# Energy_SensorRevB.net
KiCad netlist of a schematic drawn in EAGLE
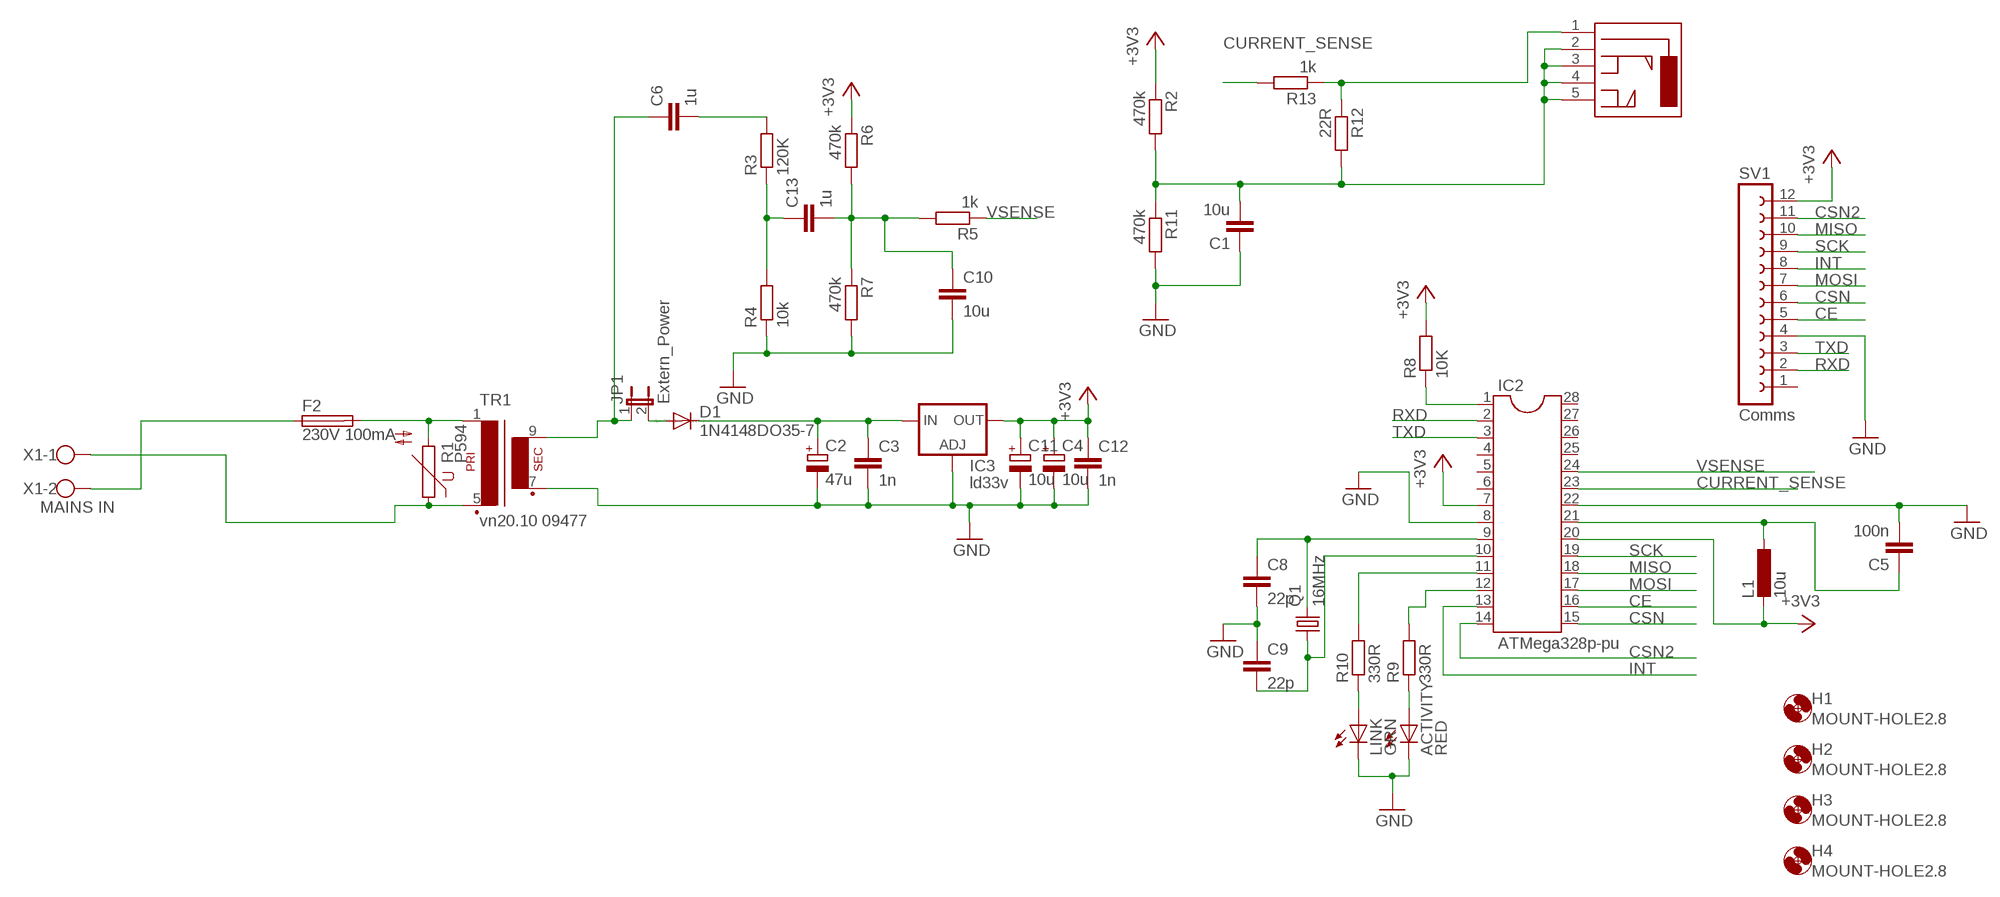
[diagram p0: schematic, sheet 1]

(export (version "E")
  (design (tool "Eeschema 10.0.6"))
  (components
    (comp (ref "ACTIVITY")
      (value "RED")
      (footprint "eagle-import:LED5MM")
      (libsource (lib "eagle-import") (part "LED5MM"))
    )
    (comp (ref "C1")
      (value "10u")
      (footprint "eagle-import:C1206K")
      (libsource (lib "eagle-import") (part "C-EUC1206K"))
    )
    (comp (ref "C2")
      (value "47u")
      (footprint "eagle-import:E3,5-10")
      (libsource (lib "eagle-import") (part "CPOL-EUE3.5-10"))
    )
    (comp (ref "C3")
      (value "1n")
      (footprint "eagle-import:C025-025X050")
      (libsource (lib "eagle-import") (part "C-EU025-025X050"))
    )
    (comp (ref "C4")
      (value "10u")
      (footprint "eagle-import:E3,5-8")
      (libsource (lib "eagle-import") (part "CPOL-EUE3.5-8"))
    )
    (comp (ref "C5")
      (value "100n")
      (footprint "eagle-import:C1206K")
      (libsource (lib "eagle-import") (part "C-EUC1206K"))
    )
    (comp (ref "C6")
      (value "1u")
      (footprint "eagle-import:C1206K")
      (libsource (lib "eagle-import") (part "C-EUC1206K"))
    )
    (comp (ref "C8")
      (value "22p")
      (footprint "eagle-import:C025-025X050")
      (libsource (lib "eagle-import") (part "C-EU025-025X050"))
    )
    (comp (ref "C9")
      (value "22p")
      (footprint "eagle-import:C025-025X050")
      (libsource (lib "eagle-import") (part "C-EU025-025X050"))
    )
    (comp (ref "C10")
      (value "10u")
      (footprint "eagle-import:C1206K")
      (libsource (lib "eagle-import") (part "C-EUC1206K"))
    )
    (comp (ref "C11")
      (value "10u")
      (footprint "eagle-import:E3,5-8")
      (libsource (lib "eagle-import") (part "CPOL-EUE3.5-8"))
    )
    (comp (ref "C12")
      (value "1n")
      (footprint "eagle-import:C025-025X050")
      (libsource (lib "eagle-import") (part "C-EU025-025X050"))
    )
    (comp (ref "C13")
      (value "1u")
      (footprint "eagle-import:C1206K")
      (libsource (lib "eagle-import") (part "C-EUC1206K"))
    )
    (comp (ref "D1")
      (value "1N4148DO35-7")
      (footprint "eagle-import:DO35-7")
      (libsource (lib "eagle-import") (part "1N4148DO35-7"))
    )
    (comp (ref "F2")
      (value "230V 100mA")
      (footprint "eagle-import:SH22,5A")
      (fields (field (name "MPN") "0031.7701.11"))
      (libsource (lib "eagle-import") (part "SH22,5A"))
    )
    (comp (ref "H1")
      (value "MOUNT-HOLE2.8")
      (footprint "eagle-import:2,8")
      (libsource (lib "eagle-import") (part "MOUNT-HOLE2.8"))
    )
    (comp (ref "H2")
      (value "MOUNT-HOLE2.8")
      (footprint "eagle-import:2,8")
      (libsource (lib "eagle-import") (part "MOUNT-HOLE2.8"))
    )
    (comp (ref "H3")
      (value "MOUNT-HOLE2.8")
      (footprint "eagle-import:2,8")
      (libsource (lib "eagle-import") (part "MOUNT-HOLE2.8"))
    )
    (comp (ref "H4")
      (value "MOUNT-HOLE2.8")
      (footprint "eagle-import:2,8")
      (libsource (lib "eagle-import") (part "MOUNT-HOLE2.8"))
    )
    (comp (ref "IC2")
      (value "ATMega328p-pu")
      (footprint "eagle-import:DIL28-3")
      (libsource (lib "eagle-import") (part "DIL28-3"))
    )
    (comp (ref "IC3")
      (value "ld33v")
      (footprint "eagle-import:317TL")
      (libsource (lib "eagle-import") (part "LM317TL"))
    )
    (comp (ref "JP1")
      (value "Extern_Power")
      (footprint "eagle-import:JP1")
      (libsource (lib "eagle-import") (part "JP1E"))
    )
    (comp (ref "L1")
      (value "10u")
      (footprint "eagle-import:L3230M")
      (libsource (lib "eagle-import") (part "L-EUL3230M"))
    )
    (comp (ref "LINK")
      (value "GRN")
      (footprint "eagle-import:LED5MM")
      (libsource (lib "eagle-import") (part "LED5MM"))
    )
    (comp (ref "Q1")
      (value "16MHz")
      (footprint "eagle-import:HC49_S")
      (libsource (lib "eagle-import") (part "CRYSTALHC49S"))
    )
    (comp (ref "R1")
      (value "P594")
      (footprint "eagle-import:P594")
      (libsource (lib "eagle-import") (part "P594"))
    )
    (comp (ref "R2")
      (value "470k")
      (footprint "eagle-import:0207_7")
      (libsource (lib "eagle-import") (part "R-EU_0207/7"))
    )
    (comp (ref "R3")
      (value "120K")
      (footprint "eagle-import:0207_7")
      (libsource (lib "eagle-import") (part "R-EU_0207/7"))
    )
    (comp (ref "R4")
      (value "10k")
      (footprint "eagle-import:0207_7")
      (libsource (lib "eagle-import") (part "R-EU_0207/7"))
    )
    (comp (ref "R5")
      (value "1k")
      (footprint "eagle-import:0207_7")
      (libsource (lib "eagle-import") (part "R-EU_0207/7"))
    )
    (comp (ref "R6")
      (value "470k")
      (footprint "eagle-import:0207_7")
      (libsource (lib "eagle-import") (part "R-EU_0207/7"))
    )
    (comp (ref "R7")
      (value "470k")
      (footprint "eagle-import:0207_7")
      (libsource (lib "eagle-import") (part "R-EU_0207/7"))
    )
    (comp (ref "R8")
      (value "10K")
      (footprint "eagle-import:0207_7")
      (libsource (lib "eagle-import") (part "R-EU_0207/7"))
    )
    (comp (ref "R9")
      (value "330R")
      (footprint "eagle-import:0207_7")
      (libsource (lib "eagle-import") (part "R-EU_0207/7"))
    )
    (comp (ref "R10")
      (value "330R")
      (footprint "eagle-import:0207_7")
      (libsource (lib "eagle-import") (part "R-EU_0207/7"))
    )
    (comp (ref "R11")
      (value "470k")
      (footprint "eagle-import:0207_7")
      (libsource (lib "eagle-import") (part "R-EU_0207/7"))
    )
    (comp (ref "R12")
      (value "22R")
      (footprint "eagle-import:R1206")
      (libsource (lib "eagle-import") (part "R-EU_R1206"))
    )
    (comp (ref "R13")
      (value "1k")
      (footprint "eagle-import:0207_7")
      (libsource (lib "eagle-import") (part "R-EU_0207/7"))
    )
    (comp (ref "SV1")
      (value "Comms")
      (footprint "eagle-import:FE12W")
      (libsource (lib "eagle-import") (part "FE12W"))
    )
    (comp (ref "TR1")
      (value "vn20.10 09477")
      (footprint "eagle-import:VV11")
      (libsource (lib "eagle-import") (part "VV11"))
    )
    (comp (ref "U$1")
      (value "3.5MMJACK")
      (footprint "eagle-import:3.5MMJACK")
      (libsource (lib "eagle-import") (part "3.5MMJACK"))
    )
    (comp (ref "X1")
      (value "MAINS IN")
      (footprint "eagle-import:W237-102")
      (fields (field (name "MPN") "237-102"))
      (libsource (lib "eagle-import") (part "W237-102"))
    )
  )
  (nets
    (net (code "1") (name "+3V3") (class "Default")
      (node (ref "C11") (pin "+") (pinfunction "+_+") (pintype "passive"))
      (node (ref "C12") (pin "1") (pinfunction "1_1") (pintype "passive"))
      (node (ref "C4") (pin "+") (pinfunction "+_+") (pintype "passive"))
      (node (ref "IC2") (pin "20") (pinfunction "20_20") (pintype "passive"))
      (node (ref "IC2") (pin "7") (pinfunction "7_7") (pintype "passive"))
      (node (ref "IC3") (pin "2") (pinfunction "OUT_2") (pintype "passive"))
      (node (ref "L1") (pin "2") (pinfunction "2_2") (pintype "passive"))
      (node (ref "R2") (pin "1") (pinfunction "1_1") (pintype "passive"))
      (node (ref "R6") (pin "1") (pinfunction "1_1") (pintype "passive"))
      (node (ref "R8") (pin "2") (pinfunction "2_2") (pintype "passive"))
      (node (ref "SV1") (pin "12") (pinfunction "12_12") (pintype "passive"))
    )
    (net (code "2") (name "/CE") (class "Default")
      (node (ref "IC2") (pin "16") (pinfunction "16_16") (pintype "passive"))
      (node (ref "SV1") (pin "5") (pinfunction "5_5") (pintype "passive"))
    )
    (net (code "3") (name "/CSN") (class "Default")
      (node (ref "IC2") (pin "15") (pinfunction "15_15") (pintype "passive"))
      (node (ref "SV1") (pin "6") (pinfunction "6_6") (pintype "passive"))
    )
    (net (code "4") (name "/CSN2") (class "Default")
      (node (ref "IC2") (pin "14") (pinfunction "14_14") (pintype "passive"))
      (node (ref "SV1") (pin "11") (pinfunction "11_11") (pintype "passive"))
    )
    (net (code "5") (name "/CURRENT_SENSE") (class "Default")
      (node (ref "IC2") (pin "23") (pinfunction "23_23") (pintype "passive"))
      (node (ref "R13") (pin "2") (pinfunction "2_2") (pintype "passive"))
    )
    (net (code "6") (name "/INT") (class "Default")
      (node (ref "IC2") (pin "13") (pinfunction "13_13") (pintype "passive"))
      (node (ref "SV1") (pin "8") (pinfunction "8_8") (pintype "passive"))
    )
    (net (code "7") (name "/MISO") (class "Default")
      (node (ref "IC2") (pin "18") (pinfunction "18_18") (pintype "passive"))
      (node (ref "SV1") (pin "10") (pinfunction "10_10") (pintype "passive"))
    )
    (net (code "8") (name "/MOSI") (class "Default")
      (node (ref "IC2") (pin "17") (pinfunction "17_17") (pintype "passive"))
      (node (ref "SV1") (pin "7") (pinfunction "7_7") (pintype "passive"))
    )
    (net (code "9") (name "/RXD") (class "Default")
      (node (ref "IC2") (pin "2") (pinfunction "2_2") (pintype "passive"))
      (node (ref "SV1") (pin "2") (pinfunction "2_2") (pintype "passive"))
    )
    (net (code "10") (name "/SCK") (class "Default")
      (node (ref "IC2") (pin "19") (pinfunction "19_19") (pintype "passive"))
      (node (ref "SV1") (pin "9") (pinfunction "9_9") (pintype "passive"))
    )
    (net (code "11") (name "/TXD") (class "Default")
      (node (ref "IC2") (pin "3") (pinfunction "3_3") (pintype "passive"))
      (node (ref "SV1") (pin "3") (pinfunction "3_3") (pintype "passive"))
    )
    (net (code "12") (name "/VSENSE") (class "Default")
      (node (ref "IC2") (pin "24") (pinfunction "24_24") (pintype "passive"))
      (node (ref "R5") (pin "1") (pinfunction "1_1") (pintype "passive"))
    )
    (net (code "13") (name "GND") (class "Default")
      (node (ref "ACTIVITY") (pin "K") (pinfunction "C_K") (pintype "passive"))
      (node (ref "C1") (pin "1") (pinfunction "1_1") (pintype "passive"))
      (node (ref "C10") (pin "2") (pinfunction "2_2") (pintype "passive"))
      (node (ref "C11") (pin "-") (pinfunction "-_-") (pintype "passive"))
      (node (ref "C12") (pin "2") (pinfunction "2_2") (pintype "passive"))
      (node (ref "C2") (pin "-") (pinfunction "-_-") (pintype "passive"))
      (node (ref "C3") (pin "2") (pinfunction "2_2") (pintype "passive"))
      (node (ref "C4") (pin "-") (pinfunction "-_-") (pintype "passive"))
      (node (ref "C5") (pin "2") (pinfunction "2_2") (pintype "passive"))
      (node (ref "C8") (pin "2") (pinfunction "2_2") (pintype "passive"))
      (node (ref "C9") (pin "1") (pinfunction "1_1") (pintype "passive"))
      (node (ref "IC2") (pin "22") (pinfunction "22_22") (pintype "passive"))
      (node (ref "IC2") (pin "8") (pinfunction "8_8") (pintype "passive"))
      (node (ref "IC3") (pin "1") (pinfunction "ADJ_1") (pintype "input"))
      (node (ref "LINK") (pin "K") (pinfunction "C_K") (pintype "passive"))
      (node (ref "R11") (pin "2") (pinfunction "2_2") (pintype "passive"))
      (node (ref "R4") (pin "1") (pinfunction "1_1") (pintype "passive"))
      (node (ref "R7") (pin "2") (pinfunction "2_2") (pintype "passive"))
      (node (ref "SV1") (pin "4") (pinfunction "4_4") (pintype "passive"))
      (node (ref "TR1") (pin "7") (pinfunction "S3_7") (pintype "passive"))
    )
    (net (code "14") (name "Net-(ACTIVITY-PadA)") (class "Default")
      (node (ref "ACTIVITY") (pin "A") (pinfunction "A_A") (pintype "passive"))
      (node (ref "R9") (pin "1") (pinfunction "1_1") (pintype "passive"))
    )
    (net (code "15") (name "Net-(C5-Pad1)") (class "Default")
      (node (ref "C5") (pin "1") (pinfunction "1_1") (pintype "passive"))
      (node (ref "IC2") (pin "21") (pinfunction "21_21") (pintype "passive"))
      (node (ref "L1") (pin "1") (pinfunction "1_1") (pintype "passive"))
    )
    (net (code "16") (name "Net-(C6-Pad2)") (class "Default")
      (node (ref "C6") (pin "2") (pinfunction "2_2") (pintype "passive"))
      (node (ref "R3") (pin "2") (pinfunction "2_2") (pintype "passive"))
    )
    (net (code "17") (name "Net-(C8-Pad1)") (class "Default")
      (node (ref "C8") (pin "1") (pinfunction "1_1") (pintype "passive"))
      (node (ref "IC2") (pin "9") (pinfunction "9_9") (pintype "passive"))
      (node (ref "Q1") (pin "2") (pinfunction "2_2") (pintype "passive"))
    )
    (net (code "18") (name "Net-(C9-Pad2)") (class "Default")
      (node (ref "C9") (pin "2") (pinfunction "2_2") (pintype "passive"))
      (node (ref "IC2") (pin "10") (pinfunction "10_10") (pintype "passive"))
      (node (ref "Q1") (pin "1") (pinfunction "1_1") (pintype "passive"))
    )
    (net (code "19") (name "Net-(C10-Pad1)") (class "Default")
      (node (ref "C10") (pin "1") (pinfunction "1_1") (pintype "passive"))
      (node (ref "C13") (pin "2") (pinfunction "2_2") (pintype "passive"))
      (node (ref "R5") (pin "2") (pinfunction "2_2") (pintype "passive"))
      (node (ref "R6") (pin "2") (pinfunction "2_2") (pintype "passive"))
      (node (ref "R7") (pin "1") (pinfunction "1_1") (pintype "passive"))
    )
    (net (code "20") (name "Net-(C13-Pad1)") (class "Default")
      (node (ref "C13") (pin "1") (pinfunction "1_1") (pintype "passive"))
      (node (ref "R3") (pin "1") (pinfunction "1_1") (pintype "passive"))
      (node (ref "R4") (pin "2") (pinfunction "2_2") (pintype "passive"))
    )
    (net (code "21") (name "Net-(D1-PadA)") (class "Default")
      (node (ref "D1") (pin "A") (pinfunction "A_A") (pintype "passive"))
      (node (ref "JP1") (pin "2") (pinfunction "2_2") (pintype "passive"))
    )
    (net (code "22") (name "Net-(IC2-Pad1)") (class "Default")
      (node (ref "IC2") (pin "1") (pinfunction "1_1") (pintype "passive"))
      (node (ref "R8") (pin "1") (pinfunction "1_1") (pintype "passive"))
    )
    (net (code "23") (name "Net-(IC2-Pad11)") (class "Default")
      (node (ref "IC2") (pin "11") (pinfunction "11_11") (pintype "passive"))
      (node (ref "R10") (pin "2") (pinfunction "2_2") (pintype "passive"))
    )
    (net (code "24") (name "Net-(IC2-Pad12)") (class "Default")
      (node (ref "IC2") (pin "12") (pinfunction "12_12") (pintype "passive"))
      (node (ref "R9") (pin "2") (pinfunction "2_2") (pintype "passive"))
    )
    (net (code "25") (name "Net-(IC3-IN)") (class "Default")
      (node (ref "C2") (pin "+") (pinfunction "+_+") (pintype "passive"))
      (node (ref "C3") (pin "1") (pinfunction "1_1") (pintype "passive"))
      (node (ref "D1") (pin "C") (pinfunction "C_C") (pintype "passive"))
      (node (ref "IC3") (pin "3") (pinfunction "IN_3") (pintype "input"))
    )
    (net (code "26") (name "Net-(LINK-PadA)") (class "Default")
      (node (ref "LINK") (pin "A") (pinfunction "A_A") (pintype "passive"))
      (node (ref "R10") (pin "1") (pinfunction "1_1") (pintype "passive"))
    )
    (net (code "27") (name "Net-(TR1-P1)") (class "Default")
      (node (ref "F2") (pin "2") (pinfunction "2_2") (pintype "passive"))
      (node (ref "R1") (pin "2") (pinfunction "2_2") (pintype "passive"))
      (node (ref "TR1") (pin "1") (pinfunction "P1_1") (pintype "passive"))
    )
    (net (code "28") (name "Net-(TR1-P2)") (class "Default")
      (node (ref "R1") (pin "1") (pinfunction "1_1") (pintype "passive"))
      (node (ref "TR1") (pin "5") (pinfunction "P2_5") (pintype "passive"))
      (node (ref "X1") (pin "1") (pinfunction "KL_1") (pintype "passive"))
    )
    (net (code "29") (name "Net-(TR1-S4)") (class "Default")
      (node (ref "C6") (pin "1") (pinfunction "1_1") (pintype "passive"))
      (node (ref "JP1") (pin "1") (pinfunction "1_1") (pintype "passive"))
      (node (ref "TR1") (pin "9") (pinfunction "S4_9") (pintype "passive"))
    )
    (net (code "30") (name "Net-(U$1-P$1)") (class "Default")
      (node (ref "R12") (pin "1") (pinfunction "1_1") (pintype "passive"))
      (node (ref "R13") (pin "1") (pinfunction "1_1") (pintype "passive"))
      (node (ref "U$1") (pin "1") (pinfunction "P$1_1") (pintype "bidirectional"))
    )
    (net (code "31") (name "Net-(U$1-P$2)") (class "Default")
      (node (ref "C1") (pin "2") (pinfunction "2_2") (pintype "passive"))
      (node (ref "R11") (pin "1") (pinfunction "1_1") (pintype "passive"))
      (node (ref "R12") (pin "2") (pinfunction "2_2") (pintype "passive"))
      (node (ref "R2") (pin "2") (pinfunction "2_2") (pintype "passive"))
      (node (ref "U$1") (pin "2") (pinfunction "P$2_2") (pintype "bidirectional"))
      (node (ref "U$1") (pin "3") (pinfunction "P$3_3") (pintype "bidirectional"))
      (node (ref "U$1") (pin "4") (pinfunction "P$4_4") (pintype "bidirectional"))
      (node (ref "U$1") (pin "5") (pinfunction "P$5_5") (pintype "bidirectional"))
    )
    (net (code "32") (name "Net-(X1B-KL)") (class "Default")
      (node (ref "F2") (pin "1") (pinfunction "1_1") (pintype "passive"))
      (node (ref "X1") (pin "2") (pinfunction "KL_2") (pintype "passive"))
    )
    (net (code "33") (name "unconnected-(IC2-Pad4)") (class "Default")
      (node (ref "IC2") (pin "4") (pinfunction "4_4") (pintype "passive"))
    )
    (net (code "34") (name "unconnected-(IC2-Pad5)") (class "Default")
      (node (ref "IC2") (pin "5") (pinfunction "5_5") (pintype "passive"))
    )
    (net (code "35") (name "unconnected-(IC2-Pad6)") (class "Default")
      (node (ref "IC2") (pin "6") (pinfunction "6_6") (pintype "passive"))
    )
    (net (code "36") (name "unconnected-(IC2-Pad25)") (class "Default")
      (node (ref "IC2") (pin "25") (pinfunction "25_25") (pintype "passive"))
    )
    (net (code "37") (name "unconnected-(IC2-Pad26)") (class "Default")
      (node (ref "IC2") (pin "26") (pinfunction "26_26") (pintype "passive"))
    )
    (net (code "38") (name "unconnected-(IC2-Pad27)") (class "Default")
      (node (ref "IC2") (pin "27") (pinfunction "27_27") (pintype "passive"))
    )
    (net (code "39") (name "unconnected-(IC2-Pad28)") (class "Default")
      (node (ref "IC2") (pin "28") (pinfunction "28_28") (pintype "passive"))
    )
    (net (code "40") (name "unconnected-(SV1-Pad1)") (class "Default")
      (node (ref "SV1") (pin "1") (pinfunction "1_1") (pintype "passive"))
    )
  )
)
